# max_helloboard.net
KiCad netlist of a schematic drawn in EAGLE
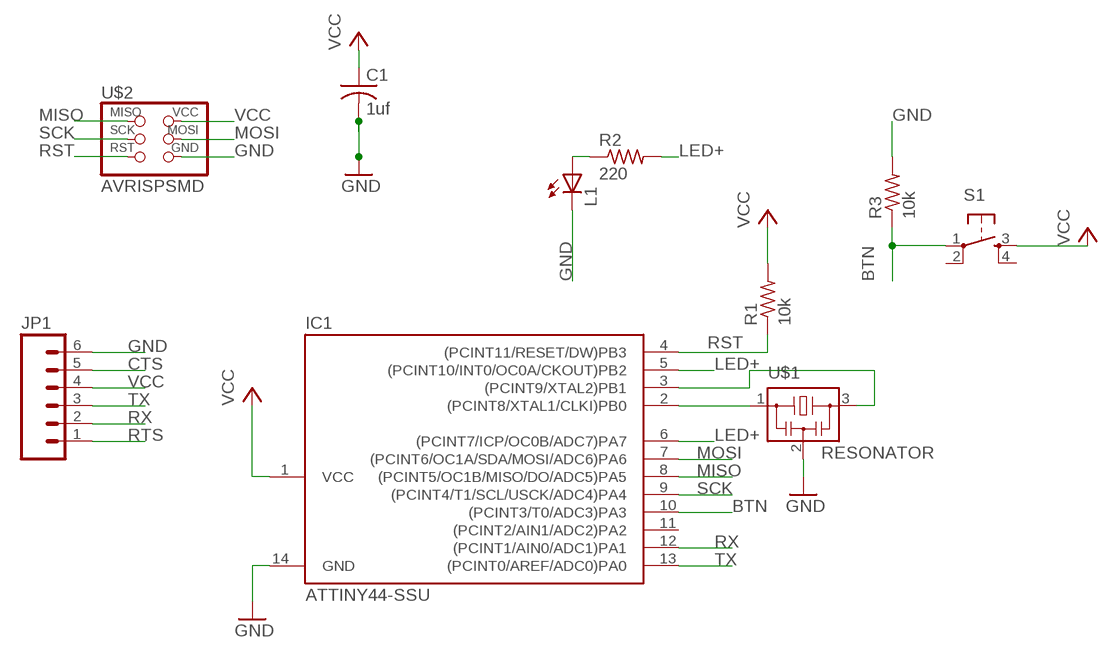
[diagram p0: schematic, sheet 1]

(export (version "E")
  (design (tool "Eeschema 10.0.6"))
  (components
    (comp (ref "C1")
      (value "1uf")
      (footprint "eagle-import:C1206")
      (libsource (lib "eagle-import") (part "C-USC1206"))
    )
    (comp (ref "IC1")
      (value "ATTINY44-SSU")
      (footprint "eagle-import:SOIC14")
      (libsource (lib "eagle-import") (part "ATTINY44-SSU"))
    )
    (comp (ref "JP1")
      (value "M06SMD")
      (footprint "eagle-import:1X06-SMD")
      (libsource (lib "eagle-import") (part "M06SMD"))
    )
    (comp (ref "L1")
      (value "LED1206")
      (footprint "eagle-import:1206")
      (libsource (lib "eagle-import") (part "LED1206"))
    )
    (comp (ref "R1")
      (value "10k")
      (footprint "eagle-import:R1206")
      (libsource (lib "eagle-import") (part "R-US_R1206"))
    )
    (comp (ref "R2")
      (value "220")
      (footprint "eagle-import:1206")
      (libsource (lib "eagle-import") (part "RESISTOR1206"))
    )
    (comp (ref "R3")
      (value "10k")
      (footprint "eagle-import:R1206")
      (libsource (lib "eagle-import") (part "R-US_R1206"))
    )
    (comp (ref "S1")
      (value "6MM_SWITCH6MM_SWITCH")
      (footprint "eagle-import:6MM_SWITCH")
      (libsource (lib "eagle-import") (part "6MM_SWITCH6MM_SWITCH"))
    )
    (comp (ref "U$1")
      (value "RESONATOR")
      (footprint "eagle-import:EFOBM")
      (libsource (lib "eagle-import") (part "RESONATOR"))
    )
    (comp (ref "U$2")
      (value "AVRISPSMD")
      (footprint "eagle-import:2X03SMD")
      (libsource (lib "eagle-import") (part "AVRISPSMD"))
    )
  )
  (nets
    (net (code "1") (name "/BTN") (class "Default")
      (node (ref "IC1") (pin "10") (pinfunction "(PCINT3/T0/ADC3)PA3_10") (pintype "bidirectional"))
      (node (ref "R3") (pin "1") (pinfunction "1_1") (pintype "passive"))
      (node (ref "S1") (pin "1") (pinfunction "P_1") (pintype "passive"))
    )
    (net (code "2") (name "/CTS") (class "Default")
      (node (ref "JP1") (pin "5") (pinfunction "5_5") (pintype "passive"))
    )
    (net (code "3") (name "/LED+") (class "Default")
      (node (ref "IC1") (pin "5") (pinfunction "(PCINT10/INT0/OC0A/CKOUT)PB2_5") (pintype "bidirectional"))
      (node (ref "IC1") (pin "6") (pinfunction "(PCINT7/ICP/OC0B/ADC7)PA7_6") (pintype "bidirectional"))
      (node (ref "R2") (pin "2") (pinfunction "2_2") (pintype "passive"))
    )
    (net (code "4") (name "/MISO") (class "Default")
      (node (ref "IC1") (pin "8") (pinfunction "(PCINT5/OC1B/MISO/DO/ADC5)PA5_8") (pintype "bidirectional"))
      (node (ref "U$2") (pin "1") (pinfunction "MISO_1") (pintype "passive"))
    )
    (net (code "5") (name "/MOSI") (class "Default")
      (node (ref "IC1") (pin "7") (pinfunction "(PCINT6/OC1A/SDA/MOSI/ADC6)PA6_7") (pintype "bidirectional"))
      (node (ref "U$2") (pin "4") (pinfunction "MOSI_4") (pintype "passive"))
    )
    (net (code "6") (name "/RST") (class "Default")
      (node (ref "IC1") (pin "4") (pinfunction "(PCINT11/RESET/DW)PB3_4") (pintype "bidirectional"))
      (node (ref "R1") (pin "1") (pinfunction "1_1") (pintype "passive"))
      (node (ref "U$2") (pin "5") (pinfunction "RST_5") (pintype "passive"))
    )
    (net (code "7") (name "/RTS") (class "Default")
      (node (ref "JP1") (pin "1") (pinfunction "1_1") (pintype "passive"))
    )
    (net (code "8") (name "/RX") (class "Default")
      (node (ref "IC1") (pin "12") (pinfunction "(PCINT1/AIN0/ADC1)PA1_12") (pintype "bidirectional"))
      (node (ref "JP1") (pin "2") (pinfunction "2_2") (pintype "passive"))
    )
    (net (code "9") (name "/SCK") (class "Default")
      (node (ref "IC1") (pin "9") (pinfunction "(PCINT4/T1/SCL/USCK/ADC4)PA4_9") (pintype "bidirectional"))
      (node (ref "U$2") (pin "3") (pinfunction "SCK_3") (pintype "passive"))
    )
    (net (code "10") (name "/TX") (class "Default")
      (node (ref "IC1") (pin "13") (pinfunction "(PCINT0/AREF/ADC0)PA0_13") (pintype "bidirectional"))
      (node (ref "JP1") (pin "3") (pinfunction "3_3") (pintype "passive"))
    )
    (net (code "11") (name "GND") (class "Default")
      (node (ref "C1") (pin "2") (pinfunction "2_2") (pintype "passive"))
      (node (ref "IC1") (pin "14") (pinfunction "GND_14") (pintype "power_in"))
      (node (ref "JP1") (pin "6") (pinfunction "6_6") (pintype "passive"))
      (node (ref "L1") (pin "2") (pinfunction "C_2") (pintype "passive"))
      (node (ref "R3") (pin "2") (pinfunction "2_2") (pintype "passive"))
      (node (ref "U$1") (pin "2") (pinfunction "2_2") (pintype "passive"))
      (node (ref "U$2") (pin "6") (pinfunction "GND_6") (pintype "passive"))
    )
    (net (code "12") (name "Net-(IC1-(PCINT8{slash}XTAL1{slash}CLKI)PB0)") (class "Default")
      (node (ref "IC1") (pin "2") (pinfunction "(PCINT8/XTAL1/CLKI)PB0_2") (pintype "bidirectional"))
      (node (ref "U$1") (pin "1") (pinfunction "1_1") (pintype "passive"))
    )
    (net (code "13") (name "Net-(IC1-(PCINT9{slash}XTAL2)PB1)") (class "Default")
      (node (ref "IC1") (pin "3") (pinfunction "(PCINT9/XTAL2)PB1_3") (pintype "bidirectional"))
      (node (ref "U$1") (pin "3") (pinfunction "3_3") (pintype "passive"))
    )
    (net (code "14") (name "Net-(L1-A)") (class "Default")
      (node (ref "L1") (pin "1") (pinfunction "A_1") (pintype "passive"))
      (node (ref "R2") (pin "1") (pinfunction "1_1") (pintype "passive"))
    )
    (net (code "15") (name "VCC") (class "Default")
      (node (ref "C1") (pin "1") (pinfunction "1_1") (pintype "passive"))
      (node (ref "IC1") (pin "1") (pinfunction "VCC_1") (pintype "power_in"))
      (node (ref "JP1") (pin "4") (pinfunction "4_4") (pintype "passive"))
      (node (ref "R1") (pin "2") (pinfunction "2_2") (pintype "passive"))
      (node (ref "S1") (pin "3") (pinfunction "S_3") (pintype "passive"))
      (node (ref "U$2") (pin "2") (pinfunction "VCC_2") (pintype "passive"))
    )
    (net (code "16") (name "unconnected-(IC1-(PCINT2{slash}AIN1{slash}ADC2)PA2-Pad11)") (class "Default")
      (node (ref "IC1") (pin "11") (pinfunction "(PCINT2/AIN1/ADC2)PA2_11") (pintype "bidirectional"))
    )
    (net (code "17") (name "unconnected-(S1-P1-Pad2)") (class "Default")
      (node (ref "S1") (pin "2") (pinfunction "P1_2") (pintype "passive"))
    )
    (net (code "18") (name "unconnected-(S1-S1-Pad4)") (class "Default")
      (node (ref "S1") (pin "4") (pinfunction "S1_4") (pintype "passive"))
    )
  )
)
